# MCU_DBG.net
KiCad netlist of a schematic drawn in Altium Designer
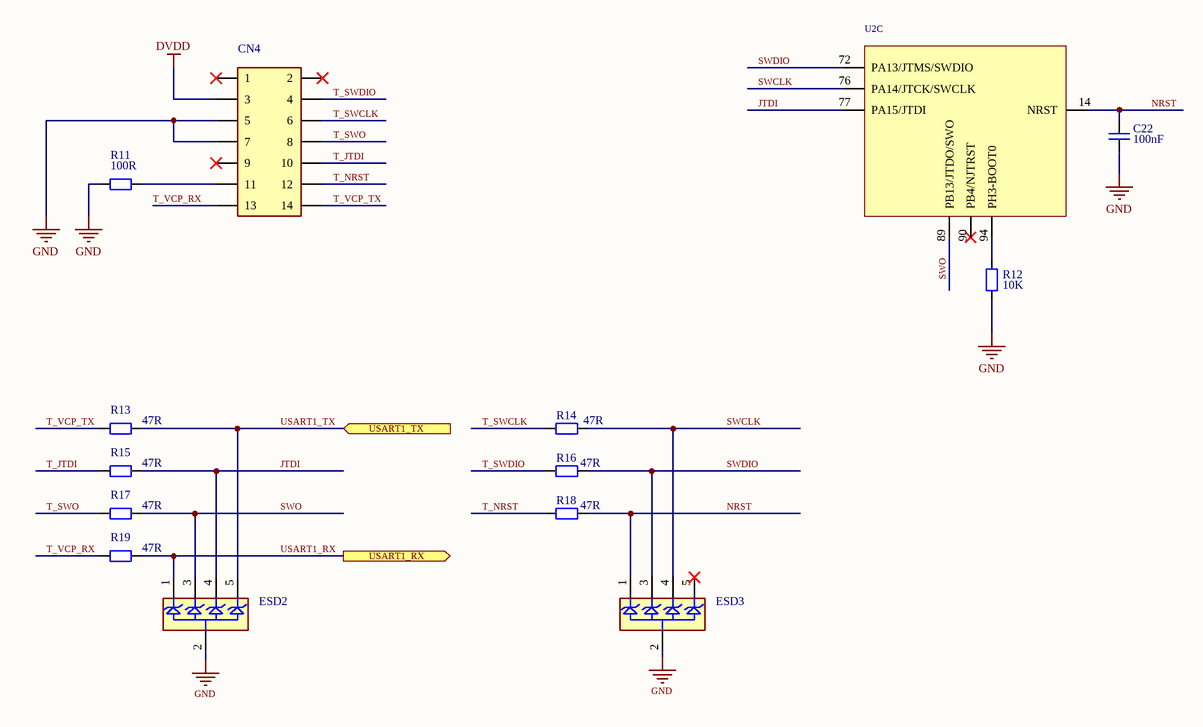
[diagram p0: MCU_DBG.SchDoc]

(export (version "E")
  (design (tool "Eeschema 10.0.6"))
  (components
    (comp (ref "C22")
      (value "100nF")
      (footprint "CAP_SM0805_YAGEOCC2_N")
      (description "CAP 100nF SM0805 X7R 50V YAGEO CC2")
      (fields
        (field (name "MANUFACTURER") "Yageo")
        (field (name "MANUFACTURER PART NUMBER") "CC0805KRX7R9BB104")
      )
      (libsource (lib "Yageo") (part "CC0805KRX7R9BB104"))
    )
    (comp (ref "CN4")
      (value "20021511-00014T4LF")
      (footprint "2002151100014T4LF")
      (description "1.27mm (0.05in.) pitch, Shrouded header, 14 contacts")
      (fields (field (name "MANUFACTURER") "Amphenol ICC"))
      (libsource (lib "header_shrouded") (part "20021511-00014T4LF"))
    )
    (comp (ref "ESD2")
      (value "ESDALC6V1W5")
      (footprint "ESDALC6V1W5")
      (fields (field (name "MANUFACTURER") "ST"))
      (libsource (lib "diode") (part "ESDALC6V1W5"))
    )
    (comp (ref "ESD3")
      (value "ESDALC6V1W5")
      (footprint "ESDALC6V1W5")
      (fields (field (name "MANUFACTURER") "ST"))
      (libsource (lib "diode") (part "ESDALC6V1W5"))
    )
    (comp (ref "R11")
      (value "100R")
      (footprint "RES_SM0805_YAGEORC_N")
      (description "RES 100R SM0805 YAGEO RC_L")
      (fields
        (field (name "MANUFACTURER") "Yageo")
        (field (name "MANUFACTURER PART NUMBER") "RC0805FR-07100RL")
      )
      (libsource (lib "Yageo") (part "RC0805FR-07100RL"))
    )
    (comp (ref "R12")
      (value "10K")
      (footprint "RES_SM0805_YAGEORC_N")
      (description "RES 10K SM0805 YAGEO RC_L")
      (fields
        (field (name "MANUFACTURER") "Yageo")
        (field (name "MANUFACTURER PART NUMBER") "RC0805FR-0710KL")
      )
      (libsource (lib "Yageo") (part "RC0805FR-0710KL"))
    )
    (comp (ref "R13")
      (value "47R")
      (footprint "RES_SM0805_YAGEORC_N")
      (description "RES 47R SM0805 YAGEO RC_L")
      (fields
        (field (name "MANUFACTURER") "Yageo")
        (field (name "MANUFACTURER PART NUMBER") "RC0805FR-0747RL")
      )
      (libsource (lib "Yageo") (part "RC0805FR-0747RL"))
    )
    (comp (ref "R14")
      (value "47R")
      (footprint "RES_SM0805_YAGEORC_N")
      (description "RES 47R SM0805 YAGEO RC_L")
      (fields
        (field (name "MANUFACTURER") "Yageo")
        (field (name "MANUFACTURER PART NUMBER") "RC0805FR-0747RL")
      )
      (libsource (lib "Yageo") (part "RC0805FR-0747RL"))
    )
    (comp (ref "R15")
      (value "47R")
      (footprint "RES_SM0805_YAGEORC_N")
      (description "RES 47R SM0805 YAGEO RC_L")
      (fields
        (field (name "MANUFACTURER") "Yageo")
        (field (name "MANUFACTURER PART NUMBER") "RC0805FR-0747RL")
      )
      (libsource (lib "Yageo") (part "RC0805FR-0747RL"))
    )
    (comp (ref "R16")
      (value "47R")
      (footprint "RES_SM0805_YAGEORC_N")
      (description "RES 47R SM0805 YAGEO RC_L")
      (fields
        (field (name "MANUFACTURER") "Yageo")
        (field (name "MANUFACTURER PART NUMBER") "RC0805FR-0747RL")
      )
      (libsource (lib "Yageo") (part "RC0805FR-0747RL"))
    )
    (comp (ref "R17")
      (value "47R")
      (footprint "RES_SM0805_YAGEORC_N")
      (description "RES 47R SM0805 YAGEO RC_L")
      (fields
        (field (name "MANUFACTURER") "Yageo")
        (field (name "MANUFACTURER PART NUMBER") "RC0805FR-0747RL")
      )
      (libsource (lib "Yageo") (part "RC0805FR-0747RL"))
    )
    (comp (ref "R18")
      (value "47R")
      (footprint "RES_SM0805_YAGEORC_N")
      (description "RES 47R SM0805 YAGEO RC_L")
      (fields
        (field (name "MANUFACTURER") "Yageo")
        (field (name "MANUFACTURER PART NUMBER") "RC0805FR-0747RL")
      )
      (libsource (lib "Yageo") (part "RC0805FR-0747RL"))
    )
    (comp (ref "R19")
      (value "47R")
      (footprint "RES_SM0805_YAGEORC_N")
      (description "RES 47R SM0805 YAGEO RC_L")
      (fields
        (field (name "MANUFACTURER") "Yageo")
        (field (name "MANUFACTURER PART NUMBER") "RC0805FR-0747RL")
      )
      (libsource (lib "Yageo") (part "RC0805FR-0747RL"))
    )
    (comp (ref "U2")
      (value "STM32U575VI_1")
      (footprint "STM32U575VI")
      (fields (field (name "MANUFACTURER") "ST") (field (name "MANUFACTURER PART NUMBER") "STM32U575VIT6Q"))
      (libsource (lib "Microcontroladores") (part "STM32U575VI_1"))
    )
  )
  (nets
    (net (code "1") (name "/JTDI") (class "Default")
      (node (ref "ESD2") (pin "4") (pinfunction "I/03_4") (pintype "passive"))
      (node (ref "R15") (pin "2") (pintype "passive"))
      (node (ref "U2") (pin "77") (pinfunction "PA15/JTDI_77") (pintype "passive"))
    )
    (net (code "2") (name "/NRST") (class "Default")
      (node (ref "C22") (pin "1") (pintype "passive"))
      (node (ref "ESD3") (pin "1") (pinfunction "I/01_1") (pintype "passive"))
      (node (ref "R18") (pin "2") (pintype "passive"))
      (node (ref "U2") (pin "14") (pinfunction "NRST_14") (pintype "passive"))
    )
    (net (code "3") (name "/SWCLK") (class "Default")
      (node (ref "ESD3") (pin "4") (pinfunction "I/03_4") (pintype "passive"))
      (node (ref "R14") (pin "2") (pintype "passive"))
      (node (ref "U2") (pin "76") (pinfunction "PA14/JTCK/SWCLK_76") (pintype "passive"))
    )
    (net (code "4") (name "/SWDIO") (class "Default")
      (node (ref "ESD3") (pin "3") (pinfunction "I/02_3") (pintype "passive"))
      (node (ref "R16") (pin "2") (pintype "passive"))
      (node (ref "U2") (pin "72") (pinfunction "PA13/JTMS/SWDIO_72") (pintype "passive"))
    )
    (net (code "5") (name "/SWO") (class "Default")
      (node (ref "ESD2") (pin "3") (pinfunction "I/02_3") (pintype "passive"))
      (node (ref "R17") (pin "2") (pintype "passive"))
      (node (ref "U2") (pin "89") (pinfunction "PB13/JTDO/SWO_89") (pintype "passive"))
    )
    (net (code "6") (name "/T_JTDI") (class "Default")
      (node (ref "CN4") (pin "10") (pinfunction "10_10") (pintype "passive"))
      (node (ref "R15") (pin "1") (pintype "passive"))
    )
    (net (code "7") (name "/T_NRST") (class "Default")
      (node (ref "CN4") (pin "12") (pinfunction "12_12") (pintype "passive"))
      (node (ref "R18") (pin "1") (pintype "passive"))
    )
    (net (code "8") (name "/T_SWCLK") (class "Default")
      (node (ref "CN4") (pin "6") (pinfunction "6_6") (pintype "passive"))
      (node (ref "R14") (pin "1") (pintype "passive"))
    )
    (net (code "9") (name "/T_SWDIO") (class "Default")
      (node (ref "CN4") (pin "4") (pinfunction "4_4") (pintype "passive"))
      (node (ref "R16") (pin "1") (pintype "passive"))
    )
    (net (code "10") (name "/T_SWO") (class "Default")
      (node (ref "CN4") (pin "8") (pinfunction "8_8") (pintype "passive"))
      (node (ref "R17") (pin "1") (pintype "passive"))
    )
    (net (code "11") (name "/T_VCP_RX") (class "Default")
      (node (ref "CN4") (pin "13") (pinfunction "13_13") (pintype "passive"))
      (node (ref "R19") (pin "1") (pintype "passive"))
    )
    (net (code "12") (name "/T_VCP_TX") (class "Default")
      (node (ref "CN4") (pin "14") (pinfunction "14_14") (pintype "passive"))
      (node (ref "R13") (pin "1") (pintype "passive"))
    )
    (net (code "13") (name "/USART1_RX") (class "Default")
      (node (ref "ESD2") (pin "1") (pinfunction "I/01_1") (pintype "passive"))
      (node (ref "R19") (pin "2") (pintype "passive"))
    )
    (net (code "14") (name "/USART1_TX") (class "Default")
      (node (ref "ESD2") (pin "5") (pinfunction "I/04_5") (pintype "passive"))
      (node (ref "R13") (pin "2") (pintype "passive"))
    )
    (net (code "15") (name "DVDD") (class "Default")
      (node (ref "CN4") (pin "3") (pinfunction "3_3") (pintype "passive"))
    )
    (net (code "16") (name "GND") (class "Default")
      (node (ref "C22") (pin "2") (pintype "passive"))
      (node (ref "CN4") (pin "5") (pinfunction "5_5") (pintype "passive"))
      (node (ref "CN4") (pin "7") (pinfunction "7_7") (pintype "passive"))
      (node (ref "ESD2") (pin "2") (pinfunction "GND_2") (pintype "passive"))
      (node (ref "ESD3") (pin "2") (pinfunction "GND_2") (pintype "passive"))
      (node (ref "R11") (pin "1") (pintype "passive"))
      (node (ref "R12") (pin "1") (pintype "passive"))
    )
    (net (code "17") (name "Net-(CN4-Pad11)") (class "Default")
      (node (ref "CN4") (pin "11") (pinfunction "11_11") (pintype "passive"))
      (node (ref "R11") (pin "2") (pintype "passive"))
    )
    (net (code "18") (name "Net-(U2C-PH3-BOOT0)") (class "Default")
      (node (ref "R12") (pin "2") (pintype "passive"))
      (node (ref "U2") (pin "94") (pinfunction "PH3-BOOT0_94") (pintype "passive"))
    )
    (net (code "19") (name "unconnected-(CN4-Pad1)") (class "Default")
      (node (ref "CN4") (pin "1") (pinfunction "1_1") (pintype "passive+no_connect"))
    )
    (net (code "20") (name "unconnected-(CN4-Pad2)") (class "Default")
      (node (ref "CN4") (pin "2") (pinfunction "2_2") (pintype "passive+no_connect"))
    )
    (net (code "21") (name "unconnected-(CN4-Pad9)") (class "Default")
      (node (ref "CN4") (pin "9") (pinfunction "9_9") (pintype "passive+no_connect"))
    )
    (net (code "22") (name "unconnected-(ESD3-I{slash}04-Pad5)") (class "Default")
      (node (ref "ESD3") (pin "5") (pinfunction "I/04_5") (pintype "passive+no_connect"))
    )
    (net (code "23") (name "unconnected-(U2C-PB4{slash}NJTRST-Pad90)") (class "Default")
      (node (ref "U2") (pin "90") (pinfunction "PB4/NJTRST_90") (pintype "passive+no_connect"))
    )
  )
)
